# M162A.net
KiCad netlist of a schematic drawn in EAGLE
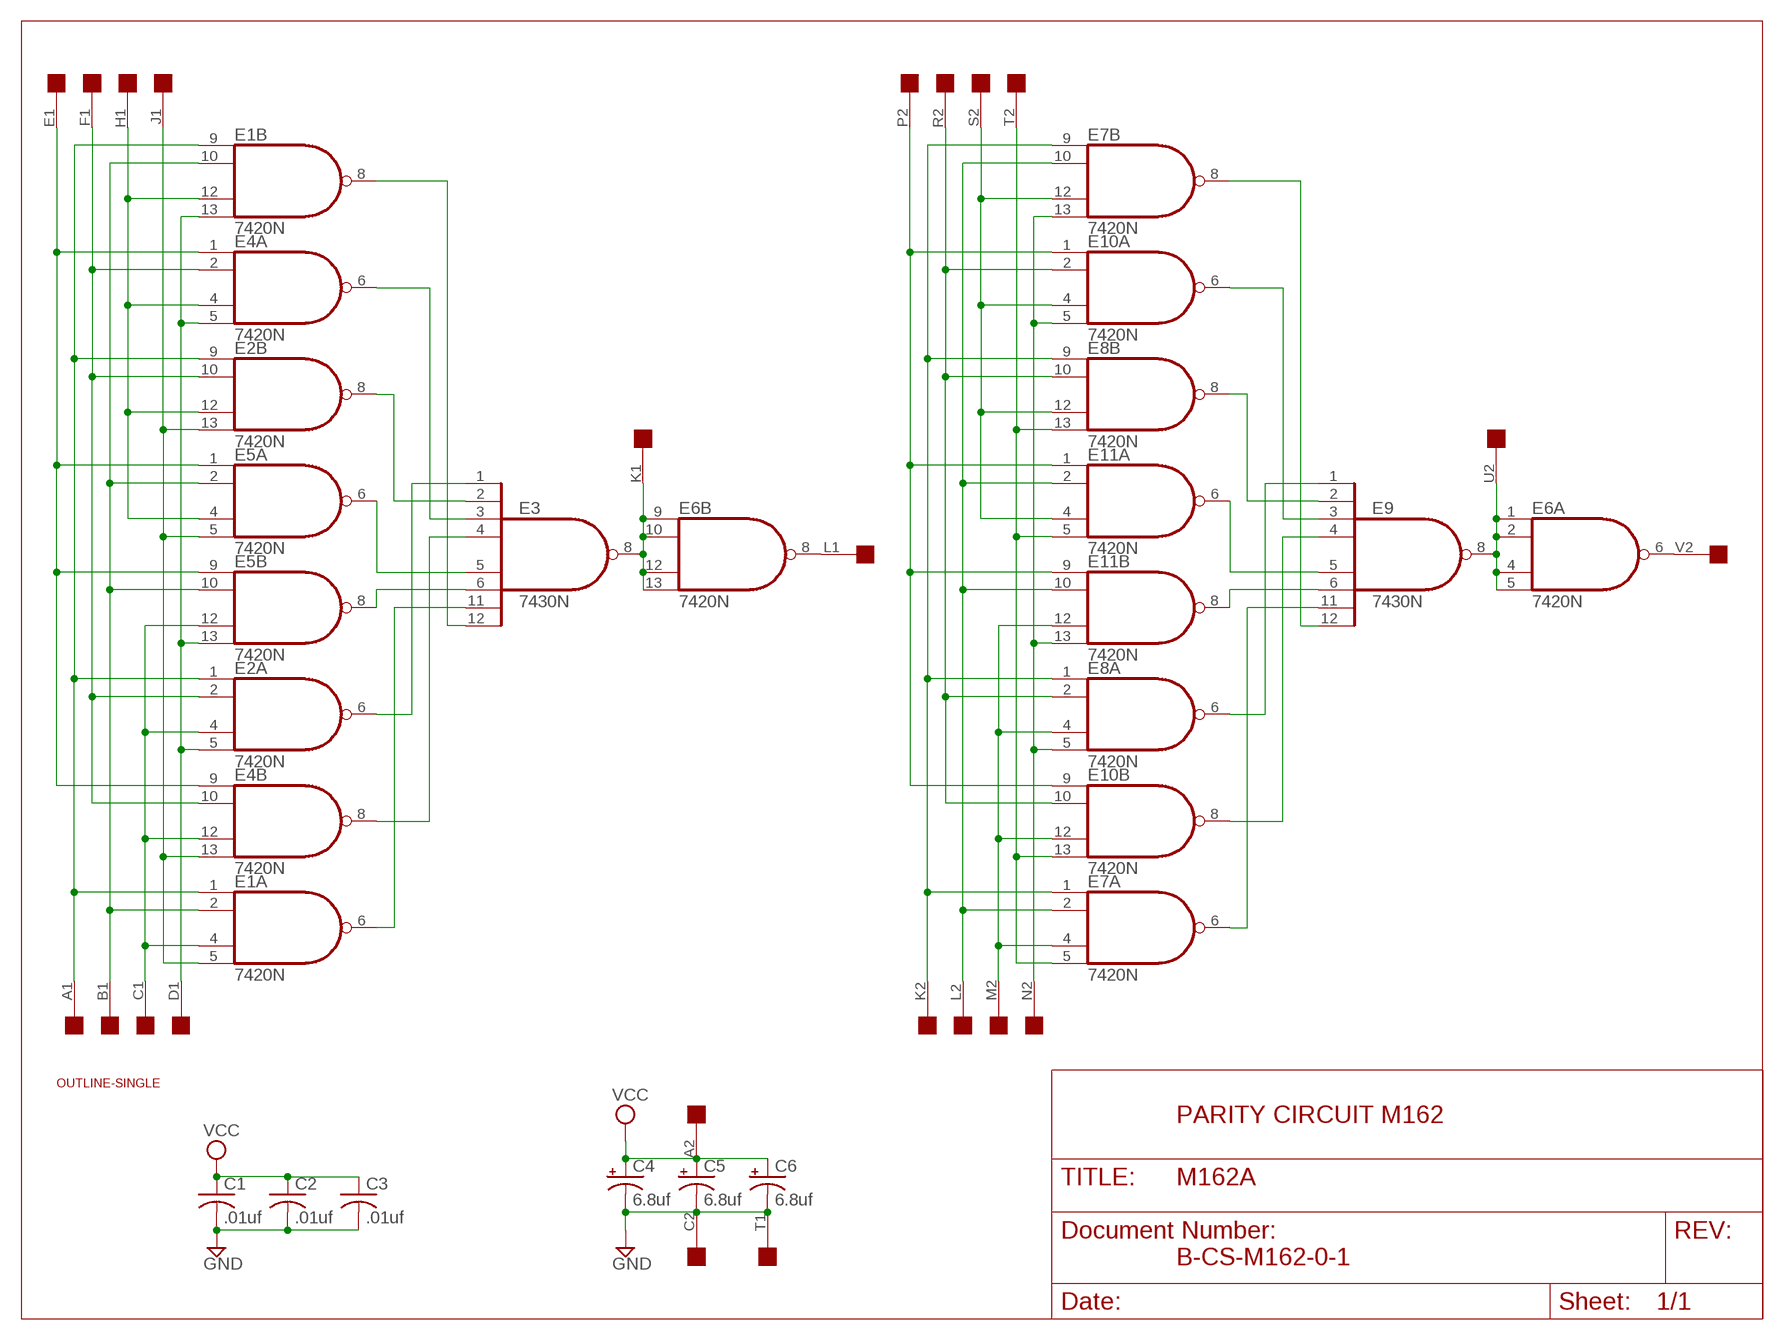
[diagram p0: schematic, sheet 1]

(export (version "E")
  (design (tool "Eeschema 10.0.6"))
  (components
    (comp (ref "C1")
      (value ".01uf")
      (footprint "eagle-import:C075-032X103")
      (libsource (lib "eagle-import") (part "C-US075-032X103"))
    )
    (comp (ref "C2")
      (value ".01uf")
      (footprint "eagle-import:C075-032X103")
      (libsource (lib "eagle-import") (part "C-US075-032X103"))
    )
    (comp (ref "C3")
      (value ".01uf")
      (footprint "eagle-import:C075-032X103")
      (libsource (lib "eagle-import") (part "C-US075-032X103"))
    )
    (comp (ref "C4")
      (value "6.8uf")
      (footprint "eagle-import:E15-5")
      (libsource (lib "eagle-import") (part "CPOL-USE15-5AXIAL"))
    )
    (comp (ref "C5")
      (value "6.8uf")
      (footprint "eagle-import:E15-5")
      (libsource (lib "eagle-import") (part "CPOL-USE15-5AXIAL"))
    )
    (comp (ref "C6")
      (value "6.8uf")
      (footprint "eagle-import:E15-5")
      (libsource (lib "eagle-import") (part "CPOL-USE15-5AXIAL"))
    )
    (comp (ref "E1")
      (value "7420N")
      (footprint "eagle-import:DIL14")
      (libsource (lib "eagle-import") (part "7420NS"))
    )
    (comp (ref "E2")
      (value "7420N")
      (footprint "eagle-import:DIL14")
      (libsource (lib "eagle-import") (part "7420NS"))
    )
    (comp (ref "E3")
      (value "7430N")
      (footprint "eagle-import:DIL14")
      (libsource (lib "eagle-import") (part "7430N"))
    )
    (comp (ref "E4")
      (value "7420N")
      (footprint "eagle-import:DIL14")
      (libsource (lib "eagle-import") (part "7420NS"))
    )
    (comp (ref "E5")
      (value "7420N")
      (footprint "eagle-import:DIL14")
      (libsource (lib "eagle-import") (part "7420NS"))
    )
    (comp (ref "E6")
      (value "7420N")
      (footprint "eagle-import:DIL14")
      (libsource (lib "eagle-import") (part "7420NS"))
    )
    (comp (ref "E7")
      (value "7420N")
      (footprint "eagle-import:DIL14")
      (libsource (lib "eagle-import") (part "7420NS"))
    )
    (comp (ref "E8")
      (value "7420N")
      (footprint "eagle-import:DIL14")
      (libsource (lib "eagle-import") (part "7420NS"))
    )
    (comp (ref "E9")
      (value "7430N")
      (footprint "eagle-import:DIL14")
      (libsource (lib "eagle-import") (part "7430N"))
    )
    (comp (ref "E10")
      (value "7420N")
      (footprint "eagle-import:DIL14")
      (libsource (lib "eagle-import") (part "7420NS"))
    )
    (comp (ref "E11")
      (value "7420N")
      (footprint "eagle-import:DIL14")
      (libsource (lib "eagle-import") (part "7420NS"))
    )
    (comp (ref "U$1")
      (value "OUTLINE-SINGLE")
      (footprint "eagle-import:SINGLE")
      (libsource (lib "eagle-import") (part "OUTLINE-SINGLE"))
    )
    (comp (ref "U$2")
      (value "EDGE-2CONNECTOR")
      (footprint "eagle-import:EDGE-CON2")
      (libsource (lib "eagle-import") (part "EDGE-2CONNECTOR"))
    )
  )
  (nets
    (net (code "1") (name "GND") (class "Default")
      (node (ref "C1") (pin "2") (pinfunction "2_2") (pintype "passive"))
      (node (ref "C2") (pin "2") (pinfunction "2_2") (pintype "passive"))
      (node (ref "C3") (pin "2") (pinfunction "2_2") (pintype "passive"))
      (node (ref "C4") (pin "-") (pinfunction "-_-") (pintype "passive"))
      (node (ref "C5") (pin "-") (pinfunction "-_-") (pintype "passive"))
      (node (ref "C6") (pin "-") (pinfunction "-_-") (pintype "passive"))
      (node (ref "U$2") (pin "C2") (pinfunction "1_C2") (pintype "bidirectional"))
      (node (ref "U$2") (pin "T1") (pinfunction "1_T1") (pintype "bidirectional"))
    )
    (net (code "2") (name "Net-(E1C-I0)") (class "Default")
      (node (ref "E1") (pin "1") (pinfunction "I0_1") (pintype "input"))
      (node (ref "E1") (pin "9") (pinfunction "I0_9") (pintype "input"))
      (node (ref "E2") (pin "1") (pinfunction "I0_1") (pintype "input"))
      (node (ref "E2") (pin "9") (pinfunction "I0_9") (pintype "input"))
      (node (ref "U$2") (pin "A1") (pinfunction "1_A1") (pintype "bidirectional"))
    )
    (net (code "3") (name "Net-(E1C-I1)") (class "Default")
      (node (ref "E1") (pin "10") (pinfunction "I1_10") (pintype "input"))
      (node (ref "E1") (pin "2") (pinfunction "I1_2") (pintype "input"))
      (node (ref "E5") (pin "10") (pinfunction "I1_10") (pintype "input"))
      (node (ref "E5") (pin "2") (pinfunction "I1_2") (pintype "input"))
      (node (ref "U$2") (pin "B1") (pinfunction "1_B1") (pintype "bidirectional"))
    )
    (net (code "4") (name "Net-(E1C-I2)") (class "Default")
      (node (ref "E1") (pin "4") (pinfunction "I2_4") (pintype "input"))
      (node (ref "E2") (pin "4") (pinfunction "I2_4") (pintype "input"))
      (node (ref "E4") (pin "12") (pinfunction "I2_12") (pintype "input"))
      (node (ref "E5") (pin "12") (pinfunction "I2_12") (pintype "input"))
      (node (ref "U$2") (pin "C1") (pinfunction "1_C1") (pintype "bidirectional"))
    )
    (net (code "5") (name "Net-(E1C-I3)") (class "Default")
      (node (ref "E1") (pin "5") (pinfunction "I3_5") (pintype "input"))
      (node (ref "E2") (pin "13") (pinfunction "I3_13") (pintype "input"))
      (node (ref "E4") (pin "13") (pinfunction "I3_13") (pintype "input"))
      (node (ref "E5") (pin "5") (pinfunction "I3_5") (pintype "input"))
      (node (ref "U$2") (pin "J1") (pinfunction "1_J1") (pintype "bidirectional"))
    )
    (net (code "6") (name "Net-(E1C-O)") (class "Default")
      (node (ref "E1") (pin "6") (pinfunction "O_6") (pintype "output"))
      (node (ref "E3") (pin "11") (pinfunction "I6_11") (pintype "input"))
    )
    (net (code "7") (name "Net-(E1D-I2)") (class "Default")
      (node (ref "E1") (pin "12") (pinfunction "I2_12") (pintype "input"))
      (node (ref "E2") (pin "12") (pinfunction "I2_12") (pintype "input"))
      (node (ref "E4") (pin "4") (pinfunction "I2_4") (pintype "input"))
      (node (ref "E5") (pin "4") (pinfunction "I2_4") (pintype "input"))
      (node (ref "U$2") (pin "H1") (pinfunction "1_H1") (pintype "bidirectional"))
    )
    (net (code "8") (name "Net-(E1D-I3)") (class "Default")
      (node (ref "E1") (pin "13") (pinfunction "I3_13") (pintype "input"))
      (node (ref "E2") (pin "5") (pinfunction "I3_5") (pintype "input"))
      (node (ref "E4") (pin "5") (pinfunction "I3_5") (pintype "input"))
      (node (ref "E5") (pin "13") (pinfunction "I3_13") (pintype "input"))
      (node (ref "U$2") (pin "D1") (pinfunction "1_D1") (pintype "bidirectional"))
    )
    (net (code "9") (name "Net-(E1D-O)") (class "Default")
      (node (ref "E1") (pin "8") (pinfunction "O_8") (pintype "output"))
      (node (ref "E3") (pin "12") (pinfunction "I7_12") (pintype "input"))
    )
    (net (code "10") (name "Net-(E2C-I1)") (class "Default")
      (node (ref "E2") (pin "10") (pinfunction "I1_10") (pintype "input"))
      (node (ref "E2") (pin "2") (pinfunction "I1_2") (pintype "input"))
      (node (ref "E4") (pin "10") (pinfunction "I1_10") (pintype "input"))
      (node (ref "E4") (pin "2") (pinfunction "I1_2") (pintype "input"))
      (node (ref "U$2") (pin "F1") (pinfunction "1_F1") (pintype "bidirectional"))
    )
    (net (code "11") (name "Net-(E2C-O)") (class "Default")
      (node (ref "E2") (pin "6") (pinfunction "O_6") (pintype "output"))
      (node (ref "E3") (pin "1") (pinfunction "I0_1") (pintype "input"))
    )
    (net (code "12") (name "Net-(E2D-O)") (class "Default")
      (node (ref "E2") (pin "8") (pinfunction "O_8") (pintype "output"))
      (node (ref "E3") (pin "2") (pinfunction "I1_2") (pintype "input"))
    )
    (net (code "13") (name "Net-(E3A-I2)") (class "Default")
      (node (ref "E3") (pin "3") (pinfunction "I2_3") (pintype "input"))
      (node (ref "E4") (pin "6") (pinfunction "O_6") (pintype "output"))
    )
    (net (code "14") (name "Net-(E3A-I3)") (class "Default")
      (node (ref "E3") (pin "4") (pinfunction "I3_4") (pintype "input"))
      (node (ref "E4") (pin "8") (pinfunction "O_8") (pintype "output"))
    )
    (net (code "15") (name "Net-(E3A-I4)") (class "Default")
      (node (ref "E3") (pin "5") (pinfunction "I4_5") (pintype "input"))
      (node (ref "E5") (pin "6") (pinfunction "O_6") (pintype "output"))
    )
    (net (code "16") (name "Net-(E3A-I5)") (class "Default")
      (node (ref "E3") (pin "6") (pinfunction "I5_6") (pintype "input"))
      (node (ref "E5") (pin "8") (pinfunction "O_8") (pintype "output"))
    )
    (net (code "17") (name "Net-(E3A-O)") (class "Default")
      (node (ref "E3") (pin "8") (pinfunction "O_8") (pintype "output"))
      (node (ref "E6") (pin "10") (pinfunction "I1_10") (pintype "input"))
      (node (ref "E6") (pin "12") (pinfunction "I2_12") (pintype "input"))
      (node (ref "E6") (pin "13") (pinfunction "I3_13") (pintype "input"))
      (node (ref "E6") (pin "9") (pinfunction "I0_9") (pintype "input"))
      (node (ref "U$2") (pin "K1") (pinfunction "1_K1") (pintype "bidirectional"))
    )
    (net (code "18") (name "Net-(E4C-I0)") (class "Default")
      (node (ref "E4") (pin "1") (pinfunction "I0_1") (pintype "input"))
      (node (ref "E4") (pin "9") (pinfunction "I0_9") (pintype "input"))
      (node (ref "E5") (pin "1") (pinfunction "I0_1") (pintype "input"))
      (node (ref "E5") (pin "9") (pinfunction "I0_9") (pintype "input"))
      (node (ref "U$2") (pin "E1") (pinfunction "1_E1") (pintype "bidirectional"))
    )
    (net (code "19") (name "Net-(E6C-I0)") (class "Default")
      (node (ref "E6") (pin "1") (pinfunction "I0_1") (pintype "input"))
      (node (ref "E6") (pin "2") (pinfunction "I1_2") (pintype "input"))
      (node (ref "E6") (pin "4") (pinfunction "I2_4") (pintype "input"))
      (node (ref "E6") (pin "5") (pinfunction "I3_5") (pintype "input"))
      (node (ref "E9") (pin "8") (pinfunction "O_8") (pintype "output"))
      (node (ref "U$2") (pin "U2") (pinfunction "1_U2") (pintype "bidirectional"))
    )
    (net (code "20") (name "Net-(E6C-O)") (class "Default")
      (node (ref "E6") (pin "6") (pinfunction "O_6") (pintype "output"))
      (node (ref "U$2") (pin "V2") (pinfunction "1_V2") (pintype "bidirectional"))
    )
    (net (code "21") (name "Net-(E6D-O)") (class "Default")
      (node (ref "E6") (pin "8") (pinfunction "O_8") (pintype "output"))
      (node (ref "U$2") (pin "L1") (pinfunction "1_L1") (pintype "bidirectional"))
    )
    (net (code "22") (name "Net-(E7C-I0)") (class "Default")
      (node (ref "E7") (pin "1") (pinfunction "I0_1") (pintype "input"))
      (node (ref "E7") (pin "9") (pinfunction "I0_9") (pintype "input"))
      (node (ref "E8") (pin "1") (pinfunction "I0_1") (pintype "input"))
      (node (ref "E8") (pin "9") (pinfunction "I0_9") (pintype "input"))
      (node (ref "U$2") (pin "K2") (pinfunction "1_K2") (pintype "bidirectional"))
    )
    (net (code "23") (name "Net-(E7C-O)") (class "Default")
      (node (ref "E7") (pin "6") (pinfunction "O_6") (pintype "output"))
      (node (ref "E9") (pin "11") (pinfunction "I6_11") (pintype "input"))
    )
    (net (code "24") (name "Net-(E7D-O)") (class "Default")
      (node (ref "E7") (pin "8") (pinfunction "O_8") (pintype "output"))
      (node (ref "E9") (pin "12") (pinfunction "I7_12") (pintype "input"))
    )
    (net (code "25") (name "Net-(E8C-O)") (class "Default")
      (node (ref "E8") (pin "6") (pinfunction "O_6") (pintype "output"))
      (node (ref "E9") (pin "1") (pinfunction "I0_1") (pintype "input"))
    )
    (net (code "26") (name "Net-(E8D-O)") (class "Default")
      (node (ref "E8") (pin "8") (pinfunction "O_8") (pintype "output"))
      (node (ref "E9") (pin "2") (pinfunction "I1_2") (pintype "input"))
    )
    (net (code "27") (name "Net-(E10C-I0)") (class "Default")
      (node (ref "E10") (pin "1") (pinfunction "I0_1") (pintype "input"))
      (node (ref "E10") (pin "9") (pinfunction "I0_9") (pintype "input"))
      (node (ref "E11") (pin "1") (pinfunction "I0_1") (pintype "input"))
      (node (ref "E11") (pin "9") (pinfunction "I0_9") (pintype "input"))
      (node (ref "U$2") (pin "P2") (pinfunction "1_P2") (pintype "bidirectional"))
    )
    (net (code "28") (name "Net-(E10C-I1)") (class "Default")
      (node (ref "E10") (pin "10") (pinfunction "I1_10") (pintype "input"))
      (node (ref "E10") (pin "2") (pinfunction "I1_2") (pintype "input"))
      (node (ref "E8") (pin "10") (pinfunction "I1_10") (pintype "input"))
      (node (ref "E8") (pin "2") (pinfunction "I1_2") (pintype "input"))
      (node (ref "U$2") (pin "R2") (pinfunction "1_R2") (pintype "bidirectional"))
    )
    (net (code "29") (name "Net-(E10C-I2)") (class "Default")
      (node (ref "E10") (pin "4") (pinfunction "I2_4") (pintype "input"))
      (node (ref "E11") (pin "4") (pinfunction "I2_4") (pintype "input"))
      (node (ref "E7") (pin "12") (pinfunction "I2_12") (pintype "input"))
      (node (ref "E8") (pin "12") (pinfunction "I2_12") (pintype "input"))
      (node (ref "U$2") (pin "S2") (pinfunction "1_S2") (pintype "bidirectional"))
    )
    (net (code "30") (name "Net-(E10C-I3)") (class "Default")
      (node (ref "E10") (pin "5") (pinfunction "I3_5") (pintype "input"))
      (node (ref "E11") (pin "13") (pinfunction "I3_13") (pintype "input"))
      (node (ref "E7") (pin "13") (pinfunction "I3_13") (pintype "input"))
      (node (ref "E8") (pin "5") (pinfunction "I3_5") (pintype "input"))
      (node (ref "U$2") (pin "N2") (pinfunction "1_N2") (pintype "bidirectional"))
    )
    (net (code "31") (name "Net-(E10C-O)") (class "Default")
      (node (ref "E10") (pin "6") (pinfunction "O_6") (pintype "output"))
      (node (ref "E9") (pin "3") (pinfunction "I2_3") (pintype "input"))
    )
    (net (code "32") (name "Net-(E10D-I2)") (class "Default")
      (node (ref "E10") (pin "12") (pinfunction "I2_12") (pintype "input"))
      (node (ref "E11") (pin "12") (pinfunction "I2_12") (pintype "input"))
      (node (ref "E7") (pin "4") (pinfunction "I2_4") (pintype "input"))
      (node (ref "E8") (pin "4") (pinfunction "I2_4") (pintype "input"))
      (node (ref "U$2") (pin "M2") (pinfunction "1_M2") (pintype "bidirectional"))
    )
    (net (code "33") (name "Net-(E10D-I3)") (class "Default")
      (node (ref "E10") (pin "13") (pinfunction "I3_13") (pintype "input"))
      (node (ref "E11") (pin "5") (pinfunction "I3_5") (pintype "input"))
      (node (ref "E7") (pin "5") (pinfunction "I3_5") (pintype "input"))
      (node (ref "E8") (pin "13") (pinfunction "I3_13") (pintype "input"))
      (node (ref "U$2") (pin "T2") (pinfunction "1_T2") (pintype "bidirectional"))
    )
    (net (code "34") (name "Net-(E10D-O)") (class "Default")
      (node (ref "E10") (pin "8") (pinfunction "O_8") (pintype "output"))
      (node (ref "E9") (pin "4") (pinfunction "I3_4") (pintype "input"))
    )
    (net (code "35") (name "Net-(E11C-I1)") (class "Default")
      (node (ref "E11") (pin "10") (pinfunction "I1_10") (pintype "input"))
      (node (ref "E11") (pin "2") (pinfunction "I1_2") (pintype "input"))
      (node (ref "E7") (pin "10") (pinfunction "I1_10") (pintype "input"))
      (node (ref "E7") (pin "2") (pinfunction "I1_2") (pintype "input"))
      (node (ref "U$2") (pin "L2") (pinfunction "1_L2") (pintype "bidirectional"))
    )
    (net (code "36") (name "Net-(E11C-O)") (class "Default")
      (node (ref "E11") (pin "6") (pinfunction "O_6") (pintype "output"))
      (node (ref "E9") (pin "5") (pinfunction "I4_5") (pintype "input"))
    )
    (net (code "37") (name "Net-(E11D-O)") (class "Default")
      (node (ref "E11") (pin "8") (pinfunction "O_8") (pintype "output"))
      (node (ref "E9") (pin "6") (pinfunction "I5_6") (pintype "input"))
    )
    (net (code "38") (name "VCC") (class "Default")
      (node (ref "C1") (pin "1") (pinfunction "1_1") (pintype "passive"))
      (node (ref "C2") (pin "1") (pinfunction "1_1") (pintype "passive"))
      (node (ref "C3") (pin "1") (pinfunction "1_1") (pintype "passive"))
      (node (ref "C4") (pin "+") (pinfunction "+_+") (pintype "passive"))
      (node (ref "C5") (pin "+") (pinfunction "+_+") (pintype "passive"))
      (node (ref "C6") (pin "+") (pinfunction "+_+") (pintype "passive"))
      (node (ref "U$2") (pin "A2") (pinfunction "1_A2") (pintype "bidirectional"))
    )
  )
)
